# FLASH.net
KiCad netlist of a schematic drawn in Altium Designer
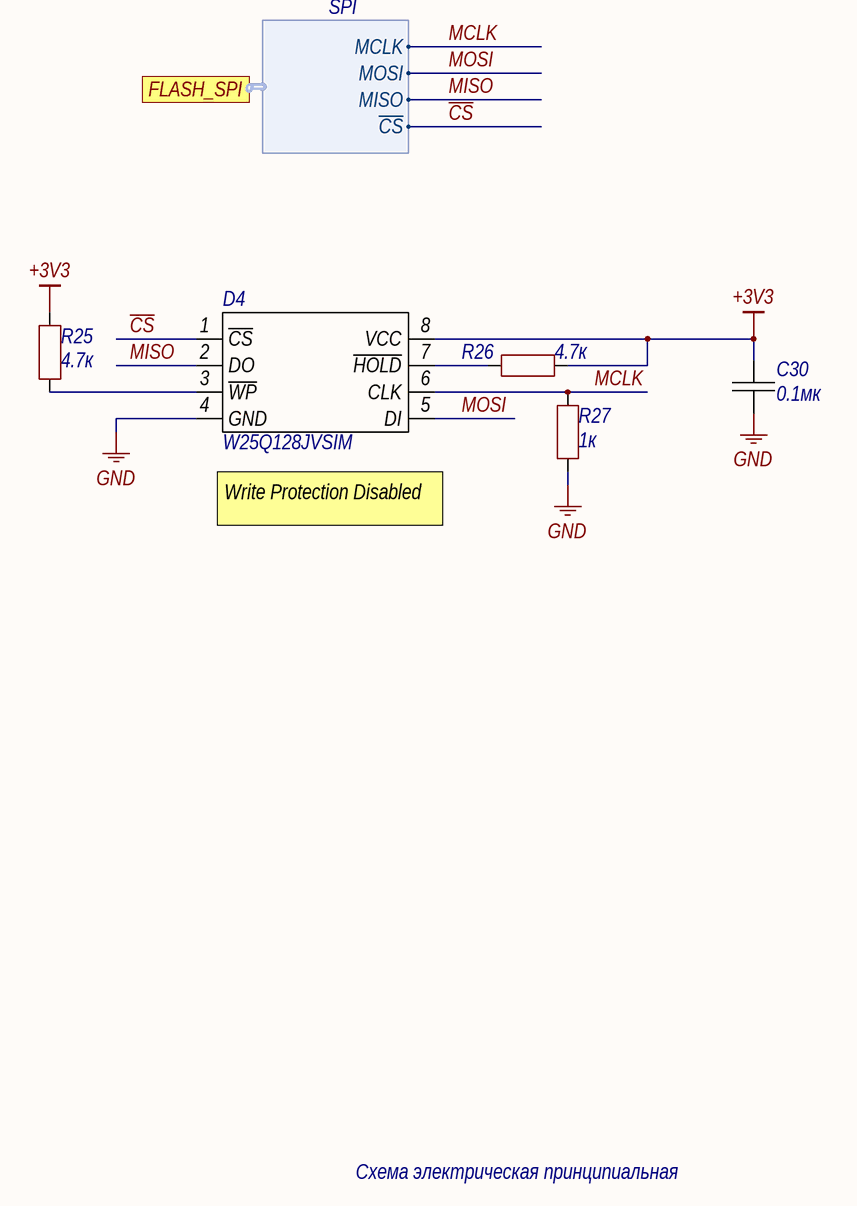
[diagram p0: FLASH.SchDoc]

(export (version "E")
  (design (tool "Eeschema 10.0.6"))
  (components
    (comp (ref "C30")
      (value "0.1мк")
      (footprint "CAP0402")
      (fields
        (field (name "MANUFACTURER") "Samsung Electro-Mechanics")
        (field (name "MPN") "CL05B104KB54PNC")
        (field (name "TOLERANCE") "10%")
      )
      (libsource (lib "Library") (part "CAPC"))
    )
    (comp (ref "D4")
      (value "~")
      (footprint "SOIC-8_208MIL_M")
      (fields
        (field (name "MPN") "W25Q128JVSIM")
        (field (name "PART NUMBER") "W25Q128JVSIM")
        (field (name "MANUFACTURER") "WINBOND")
      )
      (libsource (lib "Library") (part "D_W25Q128JVSIM"))
    )
    (comp (ref "R25")
      (value "4.7к")
      (footprint "RESC0402(1005)_M")
      (fields
        (field (name "MANUFACTURER") "UNI-ROYAL")
        (field (name "MPN") "0402WGF4701TCE")
        (field (name "POWER") "1/16W")
      )
      (libsource (lib "") (part "RES_1"))
    )
    (comp (ref "R26")
      (value "4.7к")
      (footprint "RESC0402(1005)_M")
      (fields
        (field (name "MANUFACTURER") "UNI-ROYAL")
        (field (name "MPN") "0402WGF4701TCE")
        (field (name "POWER") "1/16W")
      )
      (libsource (lib "") (part "RES_2"))
    )
    (comp (ref "R27")
      (value "1к")
      (footprint "RESC0402(1005)_M")
      (fields
        (field (name "MANUFACTURER") "UNI-ROYAL")
        (field (name "MPN") "0402WGF1001TCE")
        (field (name "POWER") "1/16W")
      )
      (libsource (lib "Library") (part "RES"))
    )
  )
  (nets
    (net (code "2") (name "+3V3") (class "Default")
      (node (ref "C30") (pin "2") (pinfunction "2_2") (pintype "passive"))
      (node (ref "D4") (pin "8") (pinfunction "VCC_8") (pintype "passive"))
      (node (ref "R25") (pin "1") (pinfunction "1_1") (pintype "passive"))
      (node (ref "R26") (pin "1") (pinfunction "1_1") (pintype "passive"))
    )
    (net (code "3") (name "/MCLK") (class "Default")
      (node (ref "D4") (pin "6") (pinfunction "CLK_6") (pintype "passive"))
      (node (ref "R27") (pin "2") (pinfunction "2_2") (pintype "passive"))
    )
    (net (code "4") (name "/MISO") (class "Default")
      (node (ref "D4") (pin "2") (pinfunction "DO_2") (pintype "passive"))
    )
    (net (code "5") (name "/MOSI") (class "Default")
      (node (ref "D4") (pin "5") (pinfunction "DI_5") (pintype "passive"))
    )
    (net (code "7") (name "/~{CS}") (class "Default")
      (node (ref "D4") (pin "1") (pinfunction "~{CS}_1") (pintype "passive"))
    )
    (net (code "8") (name "GND") (class "Default")
      (node (ref "C30") (pin "1") (pinfunction "1_1") (pintype "passive"))
      (node (ref "D4") (pin "4") (pinfunction "GND_4") (pintype "passive"))
      (node (ref "R27") (pin "1") (pinfunction "1_1") (pintype "passive"))
    )
    (net (code "9") (name "Net-(D4-~{HOLD})") (class "Default")
      (node (ref "D4") (pin "7") (pinfunction "~{HOLD}_7") (pintype "passive"))
      (node (ref "R26") (pin "2") (pinfunction "2_2") (pintype "passive"))
    )
    (net (code "10") (name "Net-(D4-~{WP})") (class "Default")
      (node (ref "D4") (pin "3") (pinfunction "~{WP}_3") (pintype "passive"))
      (node (ref "R25") (pin "2") (pinfunction "2_2") (pintype "passive"))
    )
  )
)
